# mux16_board.net
KiCad netlist of a schematic drawn in EAGLE
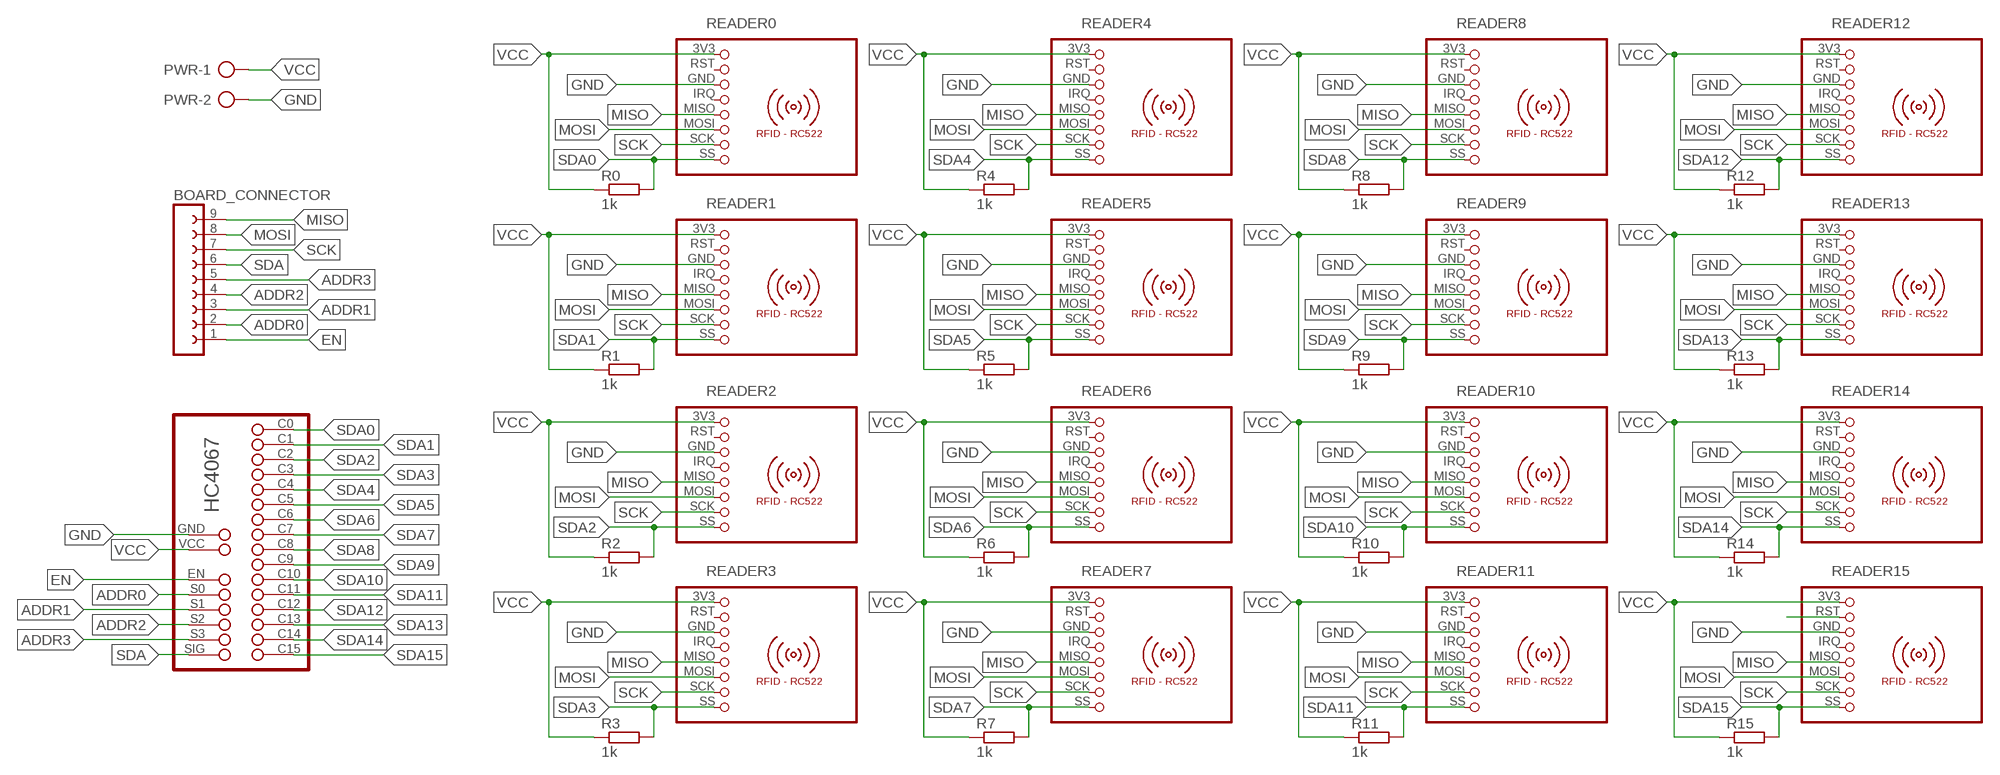
[diagram p0: schematic, sheet 1]

(export (version "E")
  (design (tool "Eeschema 10.0.6"))
  (components
    (comp (ref "BOARD_CONNECTOR")
      (value "FE09-1")
      (footprint "eagle-import:FE09")
      (libsource (lib "eagle-import") (part "FE09-1"))
    )
    (comp (ref "PWR")
      (value "AK500/2")
      (footprint "eagle-import:AK500_2")
      (libsource (lib "eagle-import") (part "AK500/2"))
    )
    (comp (ref "R0")
      (value "1k")
      (footprint "eagle-import:0207_10")
      (libsource (lib "eagle-import") (part "R-EU_0207/10"))
    )
    (comp (ref "R1")
      (value "1k")
      (footprint "eagle-import:0207_10")
      (libsource (lib "eagle-import") (part "R-EU_0207/10"))
    )
    (comp (ref "R2")
      (value "1k")
      (footprint "eagle-import:0207_10")
      (libsource (lib "eagle-import") (part "R-EU_0207/10"))
    )
    (comp (ref "R3")
      (value "1k")
      (footprint "eagle-import:0207_10")
      (libsource (lib "eagle-import") (part "R-EU_0207/10"))
    )
    (comp (ref "R4")
      (value "1k")
      (footprint "eagle-import:0207_10")
      (libsource (lib "eagle-import") (part "R-EU_0207/10"))
    )
    (comp (ref "R5")
      (value "1k")
      (footprint "eagle-import:0207_10")
      (libsource (lib "eagle-import") (part "R-EU_0207/10"))
    )
    (comp (ref "R6")
      (value "1k")
      (footprint "eagle-import:0207_10")
      (libsource (lib "eagle-import") (part "R-EU_0207/10"))
    )
    (comp (ref "R7")
      (value "1k")
      (footprint "eagle-import:0207_10")
      (libsource (lib "eagle-import") (part "R-EU_0207/10"))
    )
    (comp (ref "R8")
      (value "1k")
      (footprint "eagle-import:0207_10")
      (libsource (lib "eagle-import") (part "R-EU_0207/10"))
    )
    (comp (ref "R9")
      (value "1k")
      (footprint "eagle-import:0207_10")
      (libsource (lib "eagle-import") (part "R-EU_0207/10"))
    )
    (comp (ref "R10")
      (value "1k")
      (footprint "eagle-import:0207_10")
      (libsource (lib "eagle-import") (part "R-EU_0207/10"))
    )
    (comp (ref "R11")
      (value "1k")
      (footprint "eagle-import:0207_10")
      (libsource (lib "eagle-import") (part "R-EU_0207/10"))
    )
    (comp (ref "R12")
      (value "1k")
      (footprint "eagle-import:0207_10")
      (libsource (lib "eagle-import") (part "R-EU_0207/10"))
    )
    (comp (ref "R13")
      (value "1k")
      (footprint "eagle-import:0207_10")
      (libsource (lib "eagle-import") (part "R-EU_0207/10"))
    )
    (comp (ref "R14")
      (value "1k")
      (footprint "eagle-import:0207_10")
      (libsource (lib "eagle-import") (part "R-EU_0207/10"))
    )
    (comp (ref "R15")
      (value "1k")
      (footprint "eagle-import:0207_10")
      (libsource (lib "eagle-import") (part "R-EU_0207/10"))
    )
    (comp (ref "READER0")
      (value "RFID-RC522")
      (footprint "eagle-import:RFID-RC522")
      (libsource (lib "eagle-import") (part "RFID-RC522"))
    )
    (comp (ref "READER1")
      (value "RFID-RC522")
      (footprint "eagle-import:RFID-RC522")
      (libsource (lib "eagle-import") (part "RFID-RC522"))
    )
    (comp (ref "READER2")
      (value "RFID-RC522")
      (footprint "eagle-import:RFID-RC522")
      (libsource (lib "eagle-import") (part "RFID-RC522"))
    )
    (comp (ref "READER3")
      (value "RFID-RC522")
      (footprint "eagle-import:RFID-RC522")
      (libsource (lib "eagle-import") (part "RFID-RC522"))
    )
    (comp (ref "READER4")
      (value "RFID-RC522")
      (footprint "eagle-import:RFID-RC522")
      (libsource (lib "eagle-import") (part "RFID-RC522"))
    )
    (comp (ref "READER5")
      (value "RFID-RC522")
      (footprint "eagle-import:RFID-RC522")
      (libsource (lib "eagle-import") (part "RFID-RC522"))
    )
    (comp (ref "READER6")
      (value "RFID-RC522")
      (footprint "eagle-import:RFID-RC522")
      (libsource (lib "eagle-import") (part "RFID-RC522"))
    )
    (comp (ref "READER7")
      (value "RFID-RC522")
      (footprint "eagle-import:RFID-RC522")
      (libsource (lib "eagle-import") (part "RFID-RC522"))
    )
    (comp (ref "READER8")
      (value "RFID-RC522")
      (footprint "eagle-import:RFID-RC522")
      (libsource (lib "eagle-import") (part "RFID-RC522"))
    )
    (comp (ref "READER9")
      (value "RFID-RC522")
      (footprint "eagle-import:RFID-RC522")
      (libsource (lib "eagle-import") (part "RFID-RC522"))
    )
    (comp (ref "READER10")
      (value "RFID-RC522")
      (footprint "eagle-import:RFID-RC522")
      (libsource (lib "eagle-import") (part "RFID-RC522"))
    )
    (comp (ref "READER11")
      (value "RFID-RC522")
      (footprint "eagle-import:RFID-RC522")
      (libsource (lib "eagle-import") (part "RFID-RC522"))
    )
    (comp (ref "READER12")
      (value "RFID-RC522")
      (footprint "eagle-import:RFID-RC522")
      (libsource (lib "eagle-import") (part "RFID-RC522"))
    )
    (comp (ref "READER13")
      (value "RFID-RC522")
      (footprint "eagle-import:RFID-RC522")
      (libsource (lib "eagle-import") (part "RFID-RC522"))
    )
    (comp (ref "READER14")
      (value "RFID-RC522")
      (footprint "eagle-import:RFID-RC522")
      (libsource (lib "eagle-import") (part "RFID-RC522"))
    )
    (comp (ref "READER15")
      (value "RFID-RC522")
      (footprint "eagle-import:RFID-RC522")
      (libsource (lib "eagle-import") (part "RFID-RC522"))
    )
    (comp (ref "U$1")
      (value "HC4067_BREAKOUT_BOARD")
      (footprint "eagle-import:ANALOG_MUX_BREAKOUT_HC4067")
      (libsource (lib "eagle-import") (part "HC4067_BREAKOUT_BOARD"))
    )
  )
  (nets
    (net (code "1") (name "ADDR0") (class "Default")
      (node (ref "BOARD_CONNECTOR") (pin "2") (pinfunction "2_2") (pintype "passive"))
      (node (ref "U$1") (pin "S0") (pinfunction "S0_S0") (pintype "bidirectional"))
    )
    (net (code "2") (name "ADDR1") (class "Default")
      (node (ref "BOARD_CONNECTOR") (pin "3") (pinfunction "3_3") (pintype "passive"))
      (node (ref "U$1") (pin "S1") (pinfunction "S1_S1") (pintype "bidirectional"))
    )
    (net (code "3") (name "ADDR2") (class "Default")
      (node (ref "BOARD_CONNECTOR") (pin "4") (pinfunction "4_4") (pintype "passive"))
      (node (ref "U$1") (pin "S2") (pinfunction "S2_S2") (pintype "bidirectional"))
    )
    (net (code "4") (name "ADDR3") (class "Default")
      (node (ref "BOARD_CONNECTOR") (pin "5") (pinfunction "5_5") (pintype "passive"))
      (node (ref "U$1") (pin "S3") (pinfunction "S3_S3") (pintype "bidirectional"))
    )
    (net (code "5") (name "EN") (class "Default")
      (node (ref "BOARD_CONNECTOR") (pin "1") (pinfunction "1_1") (pintype "passive"))
      (node (ref "U$1") (pin "EN") (pinfunction "EN_EN") (pintype "bidirectional"))
    )
    (net (code "6") (name "GND") (class "Default")
      (node (ref "PWR") (pin "2") (pinfunction "KL_2") (pintype "passive"))
      (node (ref "READER0") (pin "GND") (pinfunction "3_GND") (pintype "passive"))
      (node (ref "READER1") (pin "GND") (pinfunction "3_GND") (pintype "passive"))
      (node (ref "READER10") (pin "GND") (pinfunction "3_GND") (pintype "passive"))
      (node (ref "READER11") (pin "GND") (pinfunction "3_GND") (pintype "passive"))
      (node (ref "READER12") (pin "GND") (pinfunction "3_GND") (pintype "passive"))
      (node (ref "READER13") (pin "GND") (pinfunction "3_GND") (pintype "passive"))
      (node (ref "READER14") (pin "GND") (pinfunction "3_GND") (pintype "passive"))
      (node (ref "READER15") (pin "GND") (pinfunction "3_GND") (pintype "passive"))
      (node (ref "READER2") (pin "GND") (pinfunction "3_GND") (pintype "passive"))
      (node (ref "READER3") (pin "GND") (pinfunction "3_GND") (pintype "passive"))
      (node (ref "READER4") (pin "GND") (pinfunction "3_GND") (pintype "passive"))
      (node (ref "READER5") (pin "GND") (pinfunction "3_GND") (pintype "passive"))
      (node (ref "READER6") (pin "GND") (pinfunction "3_GND") (pintype "passive"))
      (node (ref "READER7") (pin "GND") (pinfunction "3_GND") (pintype "passive"))
      (node (ref "READER8") (pin "GND") (pinfunction "3_GND") (pintype "passive"))
      (node (ref "READER9") (pin "GND") (pinfunction "3_GND") (pintype "passive"))
      (node (ref "U$1") (pin "GND") (pinfunction "GND_GND") (pintype "bidirectional"))
    )
    (net (code "7") (name "MISO") (class "Default")
      (node (ref "BOARD_CONNECTOR") (pin "9") (pinfunction "9_9") (pintype "passive"))
      (node (ref "READER0") (pin "MISO") (pinfunction "5_MISO") (pintype "passive"))
      (node (ref "READER1") (pin "MISO") (pinfunction "5_MISO") (pintype "passive"))
      (node (ref "READER10") (pin "MISO") (pinfunction "5_MISO") (pintype "passive"))
      (node (ref "READER11") (pin "MISO") (pinfunction "5_MISO") (pintype "passive"))
      (node (ref "READER12") (pin "MISO") (pinfunction "5_MISO") (pintype "passive"))
      (node (ref "READER13") (pin "MISO") (pinfunction "5_MISO") (pintype "passive"))
      (node (ref "READER14") (pin "MISO") (pinfunction "5_MISO") (pintype "passive"))
      (node (ref "READER15") (pin "MISO") (pinfunction "5_MISO") (pintype "passive"))
      (node (ref "READER2") (pin "MISO") (pinfunction "5_MISO") (pintype "passive"))
      (node (ref "READER3") (pin "MISO") (pinfunction "5_MISO") (pintype "passive"))
      (node (ref "READER4") (pin "MISO") (pinfunction "5_MISO") (pintype "passive"))
      (node (ref "READER5") (pin "MISO") (pinfunction "5_MISO") (pintype "passive"))
      (node (ref "READER6") (pin "MISO") (pinfunction "5_MISO") (pintype "passive"))
      (node (ref "READER7") (pin "MISO") (pinfunction "5_MISO") (pintype "passive"))
      (node (ref "READER8") (pin "MISO") (pinfunction "5_MISO") (pintype "passive"))
      (node (ref "READER9") (pin "MISO") (pinfunction "5_MISO") (pintype "passive"))
    )
    (net (code "8") (name "MOSI") (class "Default")
      (node (ref "BOARD_CONNECTOR") (pin "8") (pinfunction "8_8") (pintype "passive"))
      (node (ref "READER0") (pin "MOSI") (pinfunction "6_MOSI") (pintype "passive"))
      (node (ref "READER1") (pin "MOSI") (pinfunction "6_MOSI") (pintype "passive"))
      (node (ref "READER10") (pin "MOSI") (pinfunction "6_MOSI") (pintype "passive"))
      (node (ref "READER11") (pin "MOSI") (pinfunction "6_MOSI") (pintype "passive"))
      (node (ref "READER12") (pin "MOSI") (pinfunction "6_MOSI") (pintype "passive"))
      (node (ref "READER13") (pin "MOSI") (pinfunction "6_MOSI") (pintype "passive"))
      (node (ref "READER14") (pin "MOSI") (pinfunction "6_MOSI") (pintype "passive"))
      (node (ref "READER15") (pin "MOSI") (pinfunction "6_MOSI") (pintype "passive"))
      (node (ref "READER2") (pin "MOSI") (pinfunction "6_MOSI") (pintype "passive"))
      (node (ref "READER3") (pin "MOSI") (pinfunction "6_MOSI") (pintype "passive"))
      (node (ref "READER4") (pin "MOSI") (pinfunction "6_MOSI") (pintype "passive"))
      (node (ref "READER5") (pin "MOSI") (pinfunction "6_MOSI") (pintype "passive"))
      (node (ref "READER6") (pin "MOSI") (pinfunction "6_MOSI") (pintype "passive"))
      (node (ref "READER7") (pin "MOSI") (pinfunction "6_MOSI") (pintype "passive"))
      (node (ref "READER8") (pin "MOSI") (pinfunction "6_MOSI") (pintype "passive"))
      (node (ref "READER9") (pin "MOSI") (pinfunction "6_MOSI") (pintype "passive"))
    )
    (net (code "9") (name "SCK") (class "Default")
      (node (ref "BOARD_CONNECTOR") (pin "7") (pinfunction "7_7") (pintype "passive"))
      (node (ref "READER0") (pin "SCK") (pinfunction "7_SCK") (pintype "passive"))
      (node (ref "READER1") (pin "SCK") (pinfunction "7_SCK") (pintype "passive"))
      (node (ref "READER10") (pin "SCK") (pinfunction "7_SCK") (pintype "passive"))
      (node (ref "READER11") (pin "SCK") (pinfunction "7_SCK") (pintype "passive"))
      (node (ref "READER12") (pin "SCK") (pinfunction "7_SCK") (pintype "passive"))
      (node (ref "READER13") (pin "SCK") (pinfunction "7_SCK") (pintype "passive"))
      (node (ref "READER14") (pin "SCK") (pinfunction "7_SCK") (pintype "passive"))
      (node (ref "READER15") (pin "SCK") (pinfunction "7_SCK") (pintype "passive"))
      (node (ref "READER2") (pin "SCK") (pinfunction "7_SCK") (pintype "passive"))
      (node (ref "READER3") (pin "SCK") (pinfunction "7_SCK") (pintype "passive"))
      (node (ref "READER4") (pin "SCK") (pinfunction "7_SCK") (pintype "passive"))
      (node (ref "READER5") (pin "SCK") (pinfunction "7_SCK") (pintype "passive"))
      (node (ref "READER6") (pin "SCK") (pinfunction "7_SCK") (pintype "passive"))
      (node (ref "READER7") (pin "SCK") (pinfunction "7_SCK") (pintype "passive"))
      (node (ref "READER8") (pin "SCK") (pinfunction "7_SCK") (pintype "passive"))
      (node (ref "READER9") (pin "SCK") (pinfunction "7_SCK") (pintype "passive"))
    )
    (net (code "10") (name "SDA") (class "Default")
      (node (ref "BOARD_CONNECTOR") (pin "6") (pinfunction "6_6") (pintype "passive"))
      (node (ref "U$1") (pin "SIG") (pinfunction "SIG_SIG") (pintype "bidirectional"))
    )
    (net (code "11") (name "SDA0") (class "Default")
      (node (ref "R0") (pin "2") (pinfunction "2_2") (pintype "passive"))
      (node (ref "READER0") (pin "SS") (pinfunction "8_SS") (pintype "passive"))
      (node (ref "U$1") (pin "C0") (pinfunction "C0_C0") (pintype "bidirectional"))
    )
    (net (code "12") (name "SDA1") (class "Default")
      (node (ref "R1") (pin "2") (pinfunction "2_2") (pintype "passive"))
      (node (ref "READER1") (pin "SS") (pinfunction "8_SS") (pintype "passive"))
      (node (ref "U$1") (pin "C1") (pinfunction "C1_C1") (pintype "bidirectional"))
    )
    (net (code "13") (name "SDA2") (class "Default")
      (node (ref "R2") (pin "2") (pinfunction "2_2") (pintype "passive"))
      (node (ref "READER2") (pin "SS") (pinfunction "8_SS") (pintype "passive"))
      (node (ref "U$1") (pin "C2") (pinfunction "C2_C2") (pintype "bidirectional"))
    )
    (net (code "14") (name "SDA3") (class "Default")
      (node (ref "R3") (pin "2") (pinfunction "2_2") (pintype "passive"))
      (node (ref "READER3") (pin "SS") (pinfunction "8_SS") (pintype "passive"))
      (node (ref "U$1") (pin "C3") (pinfunction "C3_C3") (pintype "bidirectional"))
    )
    (net (code "15") (name "SDA4") (class "Default")
      (node (ref "R4") (pin "2") (pinfunction "2_2") (pintype "passive"))
      (node (ref "READER4") (pin "SS") (pinfunction "8_SS") (pintype "passive"))
      (node (ref "U$1") (pin "C4") (pinfunction "C4_C4") (pintype "bidirectional"))
    )
    (net (code "16") (name "SDA5") (class "Default")
      (node (ref "R5") (pin "2") (pinfunction "2_2") (pintype "passive"))
      (node (ref "READER5") (pin "SS") (pinfunction "8_SS") (pintype "passive"))
      (node (ref "U$1") (pin "C5") (pinfunction "C5_C5") (pintype "bidirectional"))
    )
    (net (code "17") (name "SDA6") (class "Default")
      (node (ref "R6") (pin "2") (pinfunction "2_2") (pintype "passive"))
      (node (ref "READER6") (pin "SS") (pinfunction "8_SS") (pintype "passive"))
      (node (ref "U$1") (pin "C6") (pinfunction "C6_C6") (pintype "bidirectional"))
    )
    (net (code "18") (name "SDA7") (class "Default")
      (node (ref "R7") (pin "2") (pinfunction "2_2") (pintype "passive"))
      (node (ref "READER7") (pin "SS") (pinfunction "8_SS") (pintype "passive"))
      (node (ref "U$1") (pin "C7") (pinfunction "C7_C7") (pintype "bidirectional"))
    )
    (net (code "19") (name "SDA8") (class "Default")
      (node (ref "R8") (pin "2") (pinfunction "2_2") (pintype "passive"))
      (node (ref "READER8") (pin "SS") (pinfunction "8_SS") (pintype "passive"))
      (node (ref "U$1") (pin "C8") (pinfunction "C8_C8") (pintype "bidirectional"))
    )
    (net (code "20") (name "SDA9") (class "Default")
      (node (ref "R9") (pin "2") (pinfunction "2_2") (pintype "passive"))
      (node (ref "READER9") (pin "SS") (pinfunction "8_SS") (pintype "passive"))
      (node (ref "U$1") (pin "C9") (pinfunction "C9_C9") (pintype "bidirectional"))
    )
    (net (code "21") (name "SDA10") (class "Default")
      (node (ref "R10") (pin "2") (pinfunction "2_2") (pintype "passive"))
      (node (ref "READER10") (pin "SS") (pinfunction "8_SS") (pintype "passive"))
      (node (ref "U$1") (pin "C10") (pinfunction "C10_C10") (pintype "bidirectional"))
    )
    (net (code "22") (name "SDA11") (class "Default")
      (node (ref "R11") (pin "2") (pinfunction "2_2") (pintype "passive"))
      (node (ref "READER11") (pin "SS") (pinfunction "8_SS") (pintype "passive"))
      (node (ref "U$1") (pin "C11") (pinfunction "C11_C11") (pintype "bidirectional"))
    )
    (net (code "23") (name "SDA12") (class "Default")
      (node (ref "R12") (pin "2") (pinfunction "2_2") (pintype "passive"))
      (node (ref "READER12") (pin "SS") (pinfunction "8_SS") (pintype "passive"))
      (node (ref "U$1") (pin "C12") (pinfunction "C12_C12") (pintype "bidirectional"))
    )
    (net (code "24") (name "SDA13") (class "Default")
      (node (ref "R13") (pin "2") (pinfunction "2_2") (pintype "passive"))
      (node (ref "READER13") (pin "SS") (pinfunction "8_SS") (pintype "passive"))
      (node (ref "U$1") (pin "C13") (pinfunction "C13_C13") (pintype "bidirectional"))
    )
    (net (code "25") (name "SDA14") (class "Default")
      (node (ref "R14") (pin "2") (pinfunction "2_2") (pintype "passive"))
      (node (ref "READER14") (pin "SS") (pinfunction "8_SS") (pintype "passive"))
      (node (ref "U$1") (pin "C14") (pinfunction "C14_C14") (pintype "bidirectional"))
    )
    (net (code "26") (name "SDA15") (class "Default")
      (node (ref "R15") (pin "2") (pinfunction "2_2") (pintype "passive"))
      (node (ref "READER15") (pin "SS") (pinfunction "8_SS") (pintype "passive"))
      (node (ref "U$1") (pin "C15") (pinfunction "C15_C15") (pintype "bidirectional"))
    )
    (net (code "27") (name "VCC") (class "Default")
      (node (ref "PWR") (pin "1") (pinfunction "KL_1") (pintype "passive"))
      (node (ref "R0") (pin "1") (pinfunction "1_1") (pintype "passive"))
      (node (ref "R1") (pin "1") (pinfunction "1_1") (pintype "passive"))
      (node (ref "R10") (pin "1") (pinfunction "1_1") (pintype "passive"))
      (node (ref "R11") (pin "1") (pinfunction "1_1") (pintype "passive"))
      (node (ref "R12") (pin "1") (pinfunction "1_1") (pintype "passive"))
      (node (ref "R13") (pin "1") (pinfunction "1_1") (pintype "passive"))
      (node (ref "R14") (pin "1") (pinfunction "1_1") (pintype "passive"))
      (node (ref "R15") (pin "1") (pinfunction "1_1") (pintype "passive"))
      (node (ref "R2") (pin "1") (pinfunction "1_1") (pintype "passive"))
      (node (ref "R3") (pin "1") (pinfunction "1_1") (pintype "passive"))
      (node (ref "R4") (pin "1") (pinfunction "1_1") (pintype "passive"))
      (node (ref "R5") (pin "1") (pinfunction "1_1") (pintype "passive"))
      (node (ref "R6") (pin "1") (pinfunction "1_1") (pintype "passive"))
      (node (ref "R7") (pin "1") (pinfunction "1_1") (pintype "passive"))
      (node (ref "R8") (pin "1") (pinfunction "1_1") (pintype "passive"))
      (node (ref "R9") (pin "1") (pinfunction "1_1") (pintype "passive"))
      (node (ref "READER0") (pin "3V3") (pinfunction "1_3V3") (pintype "passive"))
      (node (ref "READER1") (pin "3V3") (pinfunction "1_3V3") (pintype "passive"))
      (node (ref "READER10") (pin "3V3") (pinfunction "1_3V3") (pintype "passive"))
      (node (ref "READER11") (pin "3V3") (pinfunction "1_3V3") (pintype "passive"))
      (node (ref "READER12") (pin "3V3") (pinfunction "1_3V3") (pintype "passive"))
      (node (ref "READER13") (pin "3V3") (pinfunction "1_3V3") (pintype "passive"))
      (node (ref "READER14") (pin "3V3") (pinfunction "1_3V3") (pintype "passive"))
      (node (ref "READER15") (pin "3V3") (pinfunction "1_3V3") (pintype "passive"))
      (node (ref "READER2") (pin "3V3") (pinfunction "1_3V3") (pintype "passive"))
      (node (ref "READER3") (pin "3V3") (pinfunction "1_3V3") (pintype "passive"))
      (node (ref "READER4") (pin "3V3") (pinfunction "1_3V3") (pintype "passive"))
      (node (ref "READER5") (pin "3V3") (pinfunction "1_3V3") (pintype "passive"))
      (node (ref "READER6") (pin "3V3") (pinfunction "1_3V3") (pintype "passive"))
      (node (ref "READER7") (pin "3V3") (pinfunction "1_3V3") (pintype "passive"))
      (node (ref "READER8") (pin "3V3") (pinfunction "1_3V3") (pintype "passive"))
      (node (ref "READER9") (pin "3V3") (pinfunction "1_3V3") (pintype "passive"))
      (node (ref "U$1") (pin "VCC") (pinfunction "VCC_VCC") (pintype "bidirectional"))
    )
    (net (code "28") (name "unconnected-(READER0-2-PadRST)") (class "Default")
      (node (ref "READER0") (pin "RST") (pinfunction "2_RST") (pintype "passive"))
    )
    (net (code "29") (name "unconnected-(READER0-4-PadIRQ)") (class "Default")
      (node (ref "READER0") (pin "IRQ") (pinfunction "4_IRQ") (pintype "passive"))
    )
    (net (code "30") (name "unconnected-(READER1-2-PadRST)") (class "Default")
      (node (ref "READER1") (pin "RST") (pinfunction "2_RST") (pintype "passive"))
    )
    (net (code "31") (name "unconnected-(READER1-4-PadIRQ)") (class "Default")
      (node (ref "READER1") (pin "IRQ") (pinfunction "4_IRQ") (pintype "passive"))
    )
    (net (code "32") (name "unconnected-(READER2-2-PadRST)") (class "Default")
      (node (ref "READER2") (pin "RST") (pinfunction "2_RST") (pintype "passive"))
    )
    (net (code "33") (name "unconnected-(READER2-4-PadIRQ)") (class "Default")
      (node (ref "READER2") (pin "IRQ") (pinfunction "4_IRQ") (pintype "passive"))
    )
    (net (code "34") (name "unconnected-(READER3-2-PadRST)") (class "Default")
      (node (ref "READER3") (pin "RST") (pinfunction "2_RST") (pintype "passive"))
    )
    (net (code "35") (name "unconnected-(READER3-4-PadIRQ)") (class "Default")
      (node (ref "READER3") (pin "IRQ") (pinfunction "4_IRQ") (pintype "passive"))
    )
    (net (code "36") (name "unconnected-(READER4-2-PadRST)") (class "Default")
      (node (ref "READER4") (pin "RST") (pinfunction "2_RST") (pintype "passive"))
    )
    (net (code "37") (name "unconnected-(READER4-4-PadIRQ)") (class "Default")
      (node (ref "READER4") (pin "IRQ") (pinfunction "4_IRQ") (pintype "passive"))
    )
    (net (code "38") (name "unconnected-(READER5-2-PadRST)") (class "Default")
      (node (ref "READER5") (pin "RST") (pinfunction "2_RST") (pintype "passive"))
    )
    (net (code "39") (name "unconnected-(READER5-4-PadIRQ)") (class "Default")
      (node (ref "READER5") (pin "IRQ") (pinfunction "4_IRQ") (pintype "passive"))
    )
    (net (code "40") (name "unconnected-(READER6-2-PadRST)") (class "Default")
      (node (ref "READER6") (pin "RST") (pinfunction "2_RST") (pintype "passive"))
    )
    (net (code "41") (name "unconnected-(READER6-4-PadIRQ)") (class "Default")
      (node (ref "READER6") (pin "IRQ") (pinfunction "4_IRQ") (pintype "passive"))
    )
    (net (code "42") (name "unconnected-(READER7-2-PadRST)") (class "Default")
      (node (ref "READER7") (pin "RST") (pinfunction "2_RST") (pintype "passive"))
    )
    (net (code "43") (name "unconnected-(READER7-4-PadIRQ)") (class "Default")
      (node (ref "READER7") (pin "IRQ") (pinfunction "4_IRQ") (pintype "passive"))
    )
    (net (code "44") (name "unconnected-(READER8-2-PadRST)") (class "Default")
      (node (ref "READER8") (pin "RST") (pinfunction "2_RST") (pintype "passive"))
    )
    (net (code "45") (name "unconnected-(READER8-4-PadIRQ)") (class "Default")
      (node (ref "READER8") (pin "IRQ") (pinfunction "4_IRQ") (pintype "passive"))
    )
    (net (code "46") (name "unconnected-(READER9-2-PadRST)") (class "Default")
      (node (ref "READER9") (pin "RST") (pinfunction "2_RST") (pintype "passive"))
    )
    (net (code "47") (name "unconnected-(READER9-4-PadIRQ)") (class "Default")
      (node (ref "READER9") (pin "IRQ") (pinfunction "4_IRQ") (pintype "passive"))
    )
    (net (code "48") (name "unconnected-(READER10-2-PadRST)") (class "Default")
      (node (ref "READER10") (pin "RST") (pinfunction "2_RST") (pintype "passive"))
    )
    (net (code "49") (name "unconnected-(READER10-4-PadIRQ)") (class "Default")
      (node (ref "READER10") (pin "IRQ") (pinfunction "4_IRQ") (pintype "passive"))
    )
    (net (code "50") (name "unconnected-(READER11-2-PadRST)") (class "Default")
      (node (ref "READER11") (pin "RST") (pinfunction "2_RST") (pintype "passive"))
    )
    (net (code "51") (name "unconnected-(READER11-4-PadIRQ)") (class "Default")
      (node (ref "READER11") (pin "IRQ") (pinfunction "4_IRQ") (pintype "passive"))
    )
    (net (code "52") (name "unconnected-(READER12-2-PadRST)") (class "Default")
      (node (ref "READER12") (pin "RST") (pinfunction "2_RST") (pintype "passive"))
    )
    (net (code "53") (name "unconnected-(READER12-4-PadIRQ)") (class "Default")
      (node (ref "READER12") (pin "IRQ") (pinfunction "4_IRQ") (pintype "passive"))
    )
    (net (code "54") (name "unconnected-(READER13-2-PadRST)") (class "Default")
      (node (ref "READER13") (pin "RST") (pinfunction "2_RST") (pintype "passive"))
    )
    (net (code "55") (name "unconnected-(READER13-4-PadIRQ)") (class "Default")
      (node (ref "READER13") (pin "IRQ") (pinfunction "4_IRQ") (pintype "passive"))
    )
    (net (code "56") (name "unconnected-(READER14-2-PadRST)") (class "Default")
      (node (ref "READER14") (pin "RST") (pinfunction "2_RST") (pintype "passive"))
    )
    (net (code "57") (name "unconnected-(READER14-4-PadIRQ)") (class "Default")
      (node (ref "READER14") (pin "IRQ") (pinfunction "4_IRQ") (pintype "passive"))
    )
    (net (code "58") (name "unconnected-(READER15-2-PadRST)") (class "Default")
      (node (ref "READER15") (pin "RST") (pinfunction "2_RST") (pintype "passive"))
    )
    (net (code "59") (name "unconnected-(READER15-4-PadIRQ)") (class "Default")
      (node (ref "READER15") (pin "IRQ") (pinfunction "4_IRQ") (pintype "passive"))
    )
  )
)
